# 05_Wifi_Interface.net
KiCad netlist of a schematic drawn in Altium Designer
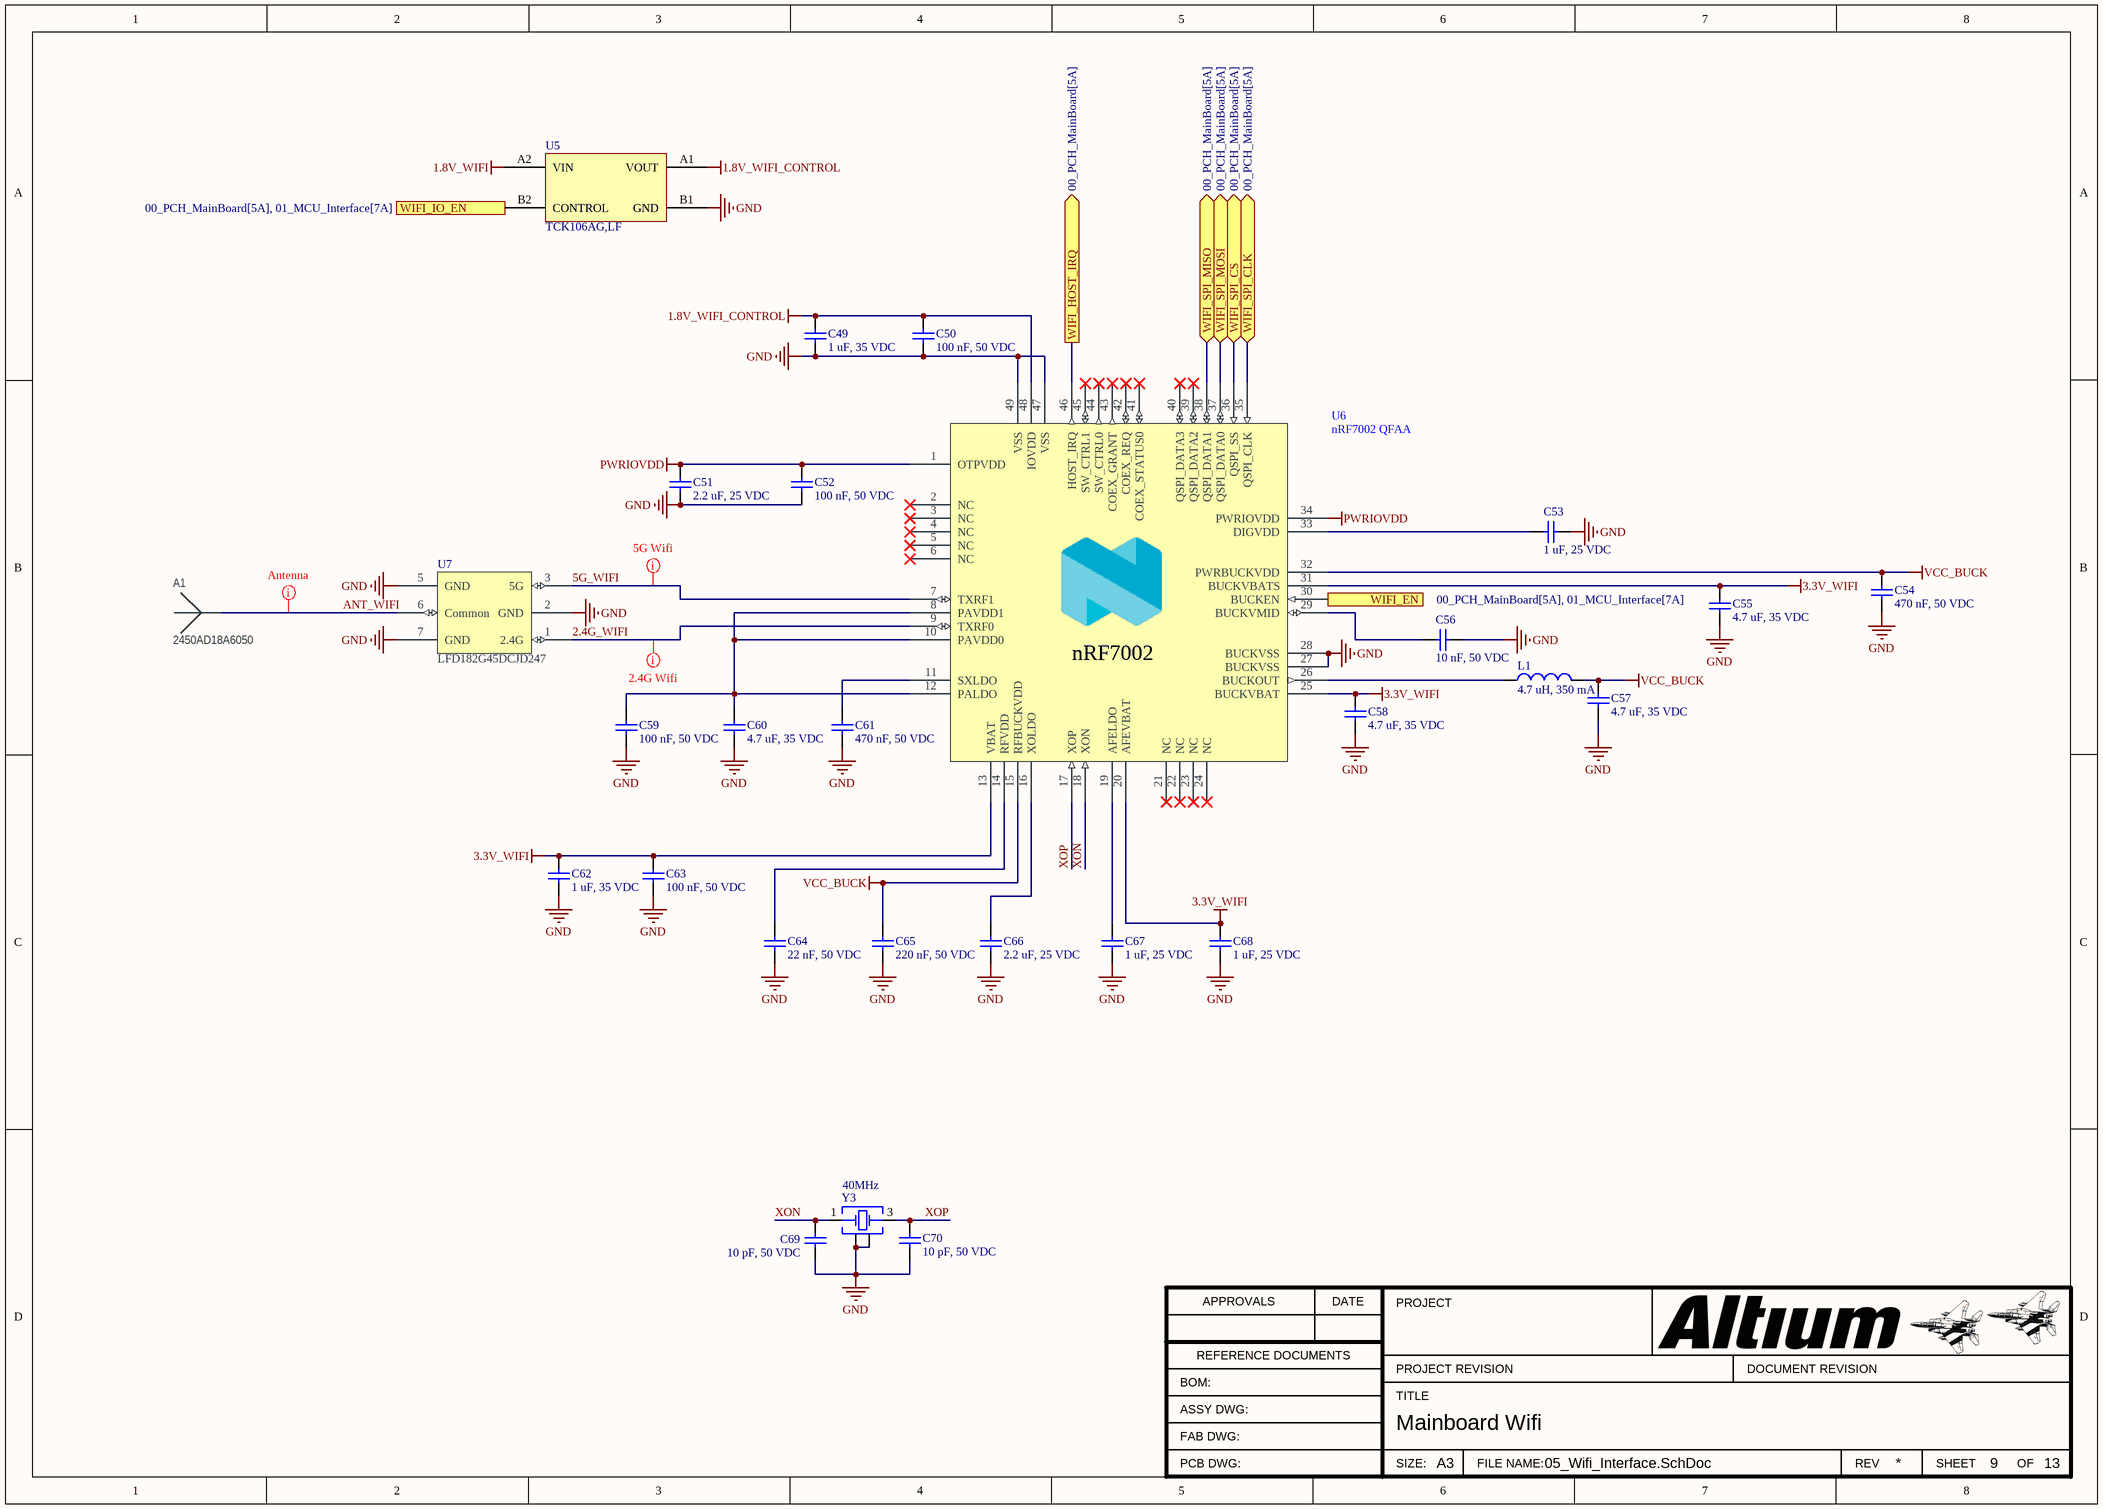
[diagram p0: 05_Wifi_Interface.SchDoc]

(export (version "E")
  (design (tool "Eeschema 10.0.6"))
  (components
    (comp (ref "A1")
      (value "2450AD18A6050")
      (footprint "2450AD18A6050")
      (description "2.4, 5, and 6GHz BT/WiFi6E Mini Antenna, Single-feed, Tri-band, Corner Mount")
      (fields (field (name "MANUFACTURER") "Johanson Technology") (field (name "AUTHOR") "hany"))
      (libsource (lib "Altium_Antenna") (part "2450AD18A6050"))
    )
    (comp (ref "C49")
      (value "1 uF, 35 VDC")
      (footprint "CAP_0603")
      (description "CAP, size 0603, 1 uF, 35 VDC")
      (fields (field (name "TOLERANCE") "+/-10%"))
      (libsource (lib "Altium_Ceramic_Cap") (part "0106031051035"))
    )
    (comp (ref "C50")
      (value "100 nF, 50 VDC")
      (footprint "CAP_0603")
      (description "CAP, size 0603, 100 nF, 50 VDC")
      (fields (field (name "TOLERANCE") "+/-10%"))
      (libsource (lib "Altium_Ceramic_Cap") (part "0106031041050"))
    )
    (comp (ref "C51")
      (value "2.2 uF, 25 VDC")
      (footprint "CAP_0603")
      (description "CAP, size 0603, 2.2 uF, 25 VDC")
      (fields (field (name "TOLERANCE") "+/-10%"))
      (libsource (lib "Altium_Ceramic_Cap") (part "0106032251025"))
    )
    (comp (ref "C52")
      (value "100 nF, 50 VDC")
      (footprint "CAP_0603")
      (description "CAP, size 0603, 100 nF, 50 VDC")
      (fields (field (name "TOLERANCE") "+/-10%"))
      (libsource (lib "Altium_Ceramic_Cap") (part "0106031041050"))
    )
    (comp (ref "C53")
      (value "1 uF, 25 VDC")
      (footprint "CAP_0603")
      (description "CAP, size 0603, 1 uF, 25 VDC")
      (fields (field (name "TOLERANCE") "+/-10%"))
      (libsource (lib "Altium_Ceramic_Cap") (part "0106031051025"))
    )
    (comp (ref "C54")
      (value "470 nF, 50 VDC")
      (footprint "CAP_0603")
      (description "CAP, size 0603, 470 nF, 50 VDC")
      (fields (field (name "TOLERANCE") "+/-10%"))
      (libsource (lib "Altium_Ceramic_Cap") (part "0106034741050"))
    )
    (comp (ref "C55")
      (value "4.7 uF, 35 VDC")
      (footprint "CAP_0603")
      (description "CAP, size 0603, 4.7 uF, 35 VDC")
      (fields (field (name "TOLERANCE") "+/-10%"))
      (libsource (lib "Altium_Ceramic_Cap") (part "0106034751035"))
    )
    (comp (ref "C56")
      (value "10 nF, 50 VDC")
      (footprint "CAP_0603")
      (description "CAP, size 0603, 10 nF, 50 VDC")
      (fields (field (name "TOLERANCE") "+/-5%"))
      (libsource (lib "Altium_Ceramic_Cap") (part "0106031030550"))
    )
    (comp (ref "C57")
      (value "4.7 uF, 35 VDC")
      (footprint "CAP_0603")
      (description "CAP, size 0603, 4.7 uF, 35 VDC")
      (fields (field (name "TOLERANCE") "+/-10%"))
      (libsource (lib "Altium_Ceramic_Cap") (part "0106034751035"))
    )
    (comp (ref "C58")
      (value "4.7 uF, 35 VDC")
      (footprint "CAP_0603")
      (description "CAP, size 0603, 4.7 uF, 35 VDC")
      (fields (field (name "TOLERANCE") "+/-10%"))
      (libsource (lib "Altium_Ceramic_Cap") (part "0106034751035"))
    )
    (comp (ref "C59")
      (value "100 nF, 50 VDC")
      (footprint "CAP_0603")
      (description "CAP, size 0603, 100 nF, 50 VDC")
      (fields (field (name "TOLERANCE") "+/-10%"))
      (libsource (lib "Altium_Ceramic_Cap") (part "0106031041050"))
    )
    (comp (ref "C60")
      (value "4.7 uF, 35 VDC")
      (footprint "CAP_0603")
      (description "CAP, size 0603, 4.7 uF, 35 VDC")
      (fields (field (name "TOLERANCE") "+/-10%"))
      (libsource (lib "Altium_Ceramic_Cap") (part "0106034751035"))
    )
    (comp (ref "C61")
      (value "470 nF, 50 VDC")
      (footprint "CAP_0603")
      (description "CAP, size 0603, 470 nF, 50 VDC")
      (fields (field (name "TOLERANCE") "+/-10%"))
      (libsource (lib "Altium_Ceramic_Cap") (part "0106034741050"))
    )
    (comp (ref "C62")
      (value "1 uF, 35 VDC")
      (footprint "CAP_0603")
      (description "CAP, size 0603, 1 uF, 35 VDC")
      (fields (field (name "TOLERANCE") "+/-10%"))
      (libsource (lib "Altium_Ceramic_Cap") (part "0106031051035"))
    )
    (comp (ref "C63")
      (value "100 nF, 50 VDC")
      (footprint "CAP_0603")
      (description "CAP, size 0603, 100 nF, 50 VDC")
      (fields (field (name "TOLERANCE") "+/-10%"))
      (libsource (lib "Altium_Ceramic_Cap") (part "0106031041050"))
    )
    (comp (ref "C64")
      (value "22 nF, 50 VDC")
      (footprint "CAP_0603")
      (description "CAP, size 0603, 22 nF, 50 VDC")
      (fields (field (name "TOLERANCE") "+/-10%"))
      (libsource (lib "Altium_Ceramic_Cap") (part "0106032231050"))
    )
    (comp (ref "C65")
      (value "220 nF, 50 VDC")
      (footprint "CAP_0603")
      (description "CAP, size 0603, 220 nF, 50 VDC")
      (fields (field (name "TOLERANCE") "+/-10%"))
      (libsource (lib "Altium_Ceramic_Cap") (part "0106032241050"))
    )
    (comp (ref "C66")
      (value "2.2 uF, 25 VDC")
      (footprint "CAP_0603")
      (description "CAP, size 0603, 2.2 uF, 25 VDC")
      (fields (field (name "TOLERANCE") "+/-10%"))
      (libsource (lib "Altium_Ceramic_Cap") (part "0106032251025"))
    )
    (comp (ref "C67")
      (value "1 uF, 25 VDC")
      (footprint "CAP_0603")
      (description "CAP, size 0603, 1 uF, 25 VDC")
      (fields (field (name "TOLERANCE") "+/-10%"))
      (libsource (lib "Altium_Ceramic_Cap") (part "0106031051025"))
    )
    (comp (ref "C68")
      (value "1 uF, 25 VDC")
      (footprint "CAP_0603")
      (description "CAP, size 0603, 1 uF, 25 VDC")
      (fields (field (name "TOLERANCE") "+/-10%"))
      (libsource (lib "Altium_Ceramic_Cap") (part "0106031051025"))
    )
    (comp (ref "C69")
      (value "10 pF, 50 VDC")
      (footprint "CAP_0603")
      (description "CAP, size 0603, 10 pF, 50 VDC")
      (fields (field (name "TOLERANCE") "+/-5%"))
      (libsource (lib "Altium_Ceramic_Cap") (part "0106031000550"))
    )
    (comp (ref "C70")
      (value "10 pF, 50 VDC")
      (footprint "CAP_0603")
      (description "CAP, size 0603, 10 pF, 50 VDC")
      (fields (field (name "TOLERANCE") "+/-5%"))
      (libsource (lib "Altium_Ceramic_Cap") (part "0106031000550"))
    )
    (comp (ref "L1")
      (value "4.7 uH, 350 mA")
      (footprint "0603")
      (description "Inductor SMD, size 0603, 4.7 uH, 350 mA")
      (fields (field (name "TOLERANCE") "20%"))
      (libsource (lib "Altium_Inductor") (part "02060347520350"))
    )
    (comp (ref "U5")
      (value "TCK106AG,LF")
      (footprint "TCK106AG,LF")
      (description "Power Switch ICs - Power Distribution Load Switch IC")
      (fields (field (name "MANUFACTURER") "Toshiba"))
      (libsource (lib "Altium_Power_Supply_IC") (part "TCK106AG,LF"))
    )
    (comp (ref "U6")
      (value "nRF7002 QFAA")
      (footprint "nRF7002")
      (description "Wifi Dual Band Companion chip")
      (fields
        (field (name "PART NUMBER") "nRF7002")
        (field (name "MANUFACTURER") "Nordic Semiconductor")
        (field (name "AUTHOR") "hany")
      )
      (libsource (lib "Nordic") (part "nRF7002"))
    )
    (comp (ref "U7")
      (value "LFD182G45DCJD247")
      (footprint "CAF-50P160X80-6N")
      (description "Signal Conditioning 2.4GHz and 5GHz Diplexer")
      (fields
        (field (name "MANUFACTURER") "Murata")
        (field (name "Comment") "LFD_Diplexer")
        (field (name "AUTHOR") "hany")
      )
      (libsource (lib "MCU_Antenna_Related") (part "LFD182G45DCJD247"))
    )
    (comp (ref "Y3")
      (value "40MHz")
      (footprint "WE-XTAL_CFPX-180")
      (description "WE-XTAL Quartz Crystal, SMT, CFPX-180, 40MHz, +/-20ppm")
      (fields
        (field (name "MANUFACTURER PART NUMBER") "NX3225SA-40M-EXS00A-CS03880")
        (field (name "MANUFACTURER") "NDK")
      )
      (libsource (lib "Altium_XTAL") (part "073525406018"))
    )
  )
  (nets
    (net (code "1") (name "/2.4G_WIFI") (class "Default")
      (node (ref "U6") (pin "9") (pinfunction "TXRF0_9") (pintype "bidirectional"))
      (node (ref "U7") (pin "1") (pinfunction "2.4G_1") (pintype "bidirectional"))
    )
    (net (code "2") (name "/5G_WIFI") (class "Default")
      (node (ref "U6") (pin "7") (pinfunction "TXRF1_7") (pintype "bidirectional"))
      (node (ref "U7") (pin "3") (pinfunction "5G_3") (pintype "bidirectional"))
    )
    (net (code "3") (name "/ANT_WIFI") (class "Default")
      (node (ref "A1") (pin "1") (pinfunction "1_1") (pintype "passive"))
      (node (ref "U7") (pin "6") (pinfunction "Common_6") (pintype "bidirectional"))
    )
    (net (code "4") (name "/WIFI_EN") (class "Default")
      (node (ref "U6") (pin "30") (pinfunction "BUCKEN_30") (pintype "input"))
    )
    (net (code "5") (name "/WIFI_HOST_IRQ") (class "Default")
      (node (ref "U6") (pin "46") (pinfunction "HOST_IRQ_46") (pintype "output"))
    )
    (net (code "6") (name "/WIFI_IO_EN") (class "Default")
      (node (ref "U5") (pin "B2") (pinfunction "CONTROL_B2") (pintype "passive"))
    )
    (net (code "7") (name "/WIFI_SPI_CLK") (class "Default")
      (node (ref "U6") (pin "35") (pinfunction "QSPI_CLK_35") (pintype "input"))
    )
    (net (code "8") (name "/WIFI_SPI_CS") (class "Default")
      (node (ref "U6") (pin "36") (pinfunction "QSPI_SS_36") (pintype "input"))
    )
    (net (code "9") (name "/WIFI_SPI_MISO") (class "Default")
      (node (ref "U6") (pin "38") (pinfunction "QSPI_DATA1_38") (pintype "bidirectional"))
    )
    (net (code "10") (name "/WIFI_SPI_MOSI") (class "Default")
      (node (ref "U6") (pin "37") (pinfunction "QSPI_DATA0_37") (pintype "bidirectional"))
    )
    (net (code "11") (name "/XON") (class "Default")
      (node (ref "C69") (pin "2") (pinfunction "2_2") (pintype "passive"))
      (node (ref "U6") (pin "18") (pinfunction "XON_18") (pintype "input"))
      (node (ref "Y3") (pin "1") (pinfunction "Crystal_1") (pintype "passive"))
    )
    (net (code "12") (name "/XOP") (class "Default")
      (node (ref "C70") (pin "2") (pinfunction "2_2") (pintype "passive"))
      (node (ref "U6") (pin "17") (pinfunction "XOP_17") (pintype "input"))
      (node (ref "Y3") (pin "3") (pinfunction "Crystal_3") (pintype "passive"))
    )
    (net (code "13") (name "1.8V_WIFI") (class "Default")
      (node (ref "U5") (pin "A2") (pinfunction "VIN_A2") (pintype "passive"))
    )
    (net (code "14") (name "1.8V_WIFI_CONTROL") (class "Default")
      (node (ref "C49") (pin "2") (pinfunction "2_2") (pintype "passive"))
      (node (ref "C50") (pin "2") (pinfunction "2_2") (pintype "passive"))
      (node (ref "U5") (pin "A1") (pinfunction "VOUT_A1") (pintype "passive"))
      (node (ref "U6") (pin "48") (pinfunction "IOVDD_48") (pintype "power_in"))
    )
    (net (code "15") (name "3.3V_WIFI") (class "Default")
      (node (ref "C55") (pin "2") (pinfunction "2_2") (pintype "passive"))
      (node (ref "C58") (pin "2") (pinfunction "2_2") (pintype "passive"))
      (node (ref "C62") (pin "2") (pinfunction "2_2") (pintype "passive"))
      (node (ref "C63") (pin "2") (pinfunction "2_2") (pintype "passive"))
      (node (ref "C68") (pin "2") (pinfunction "2_2") (pintype "passive"))
      (node (ref "U6") (pin "13") (pinfunction "VBAT_13") (pintype "power_in"))
      (node (ref "U6") (pin "20") (pinfunction "AFEVBAT_20") (pintype "power_in"))
      (node (ref "U6") (pin "25") (pinfunction "BUCKVBAT_25") (pintype "power_in"))
      (node (ref "U6") (pin "31") (pinfunction "BUCKVBATS_31") (pintype "power_in"))
    )
    (net (code "16") (name "GND") (class "Default")
      (node (ref "C49") (pin "1") (pinfunction "1_1") (pintype "passive"))
      (node (ref "C50") (pin "1") (pinfunction "1_1") (pintype "passive"))
      (node (ref "C51") (pin "1") (pinfunction "1_1") (pintype "passive"))
      (node (ref "C52") (pin "1") (pinfunction "1_1") (pintype "passive"))
      (node (ref "C53") (pin "2") (pinfunction "2_2") (pintype "passive"))
      (node (ref "C54") (pin "1") (pinfunction "1_1") (pintype "passive"))
      (node (ref "C55") (pin "1") (pinfunction "1_1") (pintype "passive"))
      (node (ref "C56") (pin "2") (pinfunction "2_2") (pintype "passive"))
      (node (ref "C57") (pin "1") (pinfunction "1_1") (pintype "passive"))
      (node (ref "C58") (pin "1") (pinfunction "1_1") (pintype "passive"))
      (node (ref "C59") (pin "1") (pinfunction "1_1") (pintype "passive"))
      (node (ref "C60") (pin "1") (pinfunction "1_1") (pintype "passive"))
      (node (ref "C61") (pin "1") (pinfunction "1_1") (pintype "passive"))
      (node (ref "C62") (pin "1") (pinfunction "1_1") (pintype "passive"))
      (node (ref "C63") (pin "1") (pinfunction "1_1") (pintype "passive"))
      (node (ref "C64") (pin "1") (pinfunction "1_1") (pintype "passive"))
      (node (ref "C65") (pin "1") (pinfunction "1_1") (pintype "passive"))
      (node (ref "C66") (pin "1") (pinfunction "1_1") (pintype "passive"))
      (node (ref "C67") (pin "1") (pinfunction "1_1") (pintype "passive"))
      (node (ref "C68") (pin "1") (pinfunction "1_1") (pintype "passive"))
      (node (ref "C69") (pin "1") (pinfunction "1_1") (pintype "passive"))
      (node (ref "C70") (pin "1") (pinfunction "1_1") (pintype "passive"))
      (node (ref "U5") (pin "B1") (pinfunction "GND_B1") (pintype "passive"))
      (node (ref "U6") (pin "27") (pinfunction "BUCKVSS_27") (pintype "power_in"))
      (node (ref "U6") (pin "28") (pinfunction "BUCKVSS_28") (pintype "power_in"))
      (node (ref "U6") (pin "47") (pinfunction "VSS_47") (pintype "passive"))
      (node (ref "U6") (pin "49") (pinfunction "VSS_49") (pintype "power_in"))
      (node (ref "U7") (pin "2") (pinfunction "GND_2") (pintype "power_in"))
      (node (ref "U7") (pin "5") (pinfunction "GND_5") (pintype "power_in"))
      (node (ref "U7") (pin "7") (pinfunction "GND_7") (pintype "power_in"))
      (node (ref "Y3") (pin "2") (pinfunction "GND_2") (pintype "passive"))
      (node (ref "Y3") (pin "4") (pinfunction "GND_4") (pintype "passive"))
    )
    (net (code "17") (name "Net-(U6-AFELDO)") (class "Default")
      (node (ref "C67") (pin "2") (pinfunction "2_2") (pintype "passive"))
      (node (ref "U6") (pin "19") (pinfunction "AFELDO_19") (pintype "power_in"))
    )
    (net (code "18") (name "Net-(U6-BUCKOUT)") (class "Default")
      (node (ref "L1") (pin "1") (pinfunction "1_1") (pintype "passive"))
      (node (ref "U6") (pin "26") (pinfunction "BUCKOUT_26") (pintype "output"))
    )
    (net (code "19") (name "Net-(U6-BUCKVMID)") (class "Default")
      (node (ref "C56") (pin "1") (pinfunction "1_1") (pintype "passive"))
      (node (ref "U6") (pin "29") (pinfunction "BUCKVMID_29") (pintype "bidirectional"))
    )
    (net (code "20") (name "Net-(U6-DIGVDD)") (class "Default")
      (node (ref "C53") (pin "1") (pinfunction "1_1") (pintype "passive"))
      (node (ref "U6") (pin "33") (pinfunction "DIGVDD_33") (pintype "power_in"))
    )
    (net (code "21") (name "Net-(U6-PALDO)") (class "Default")
      (node (ref "C59") (pin "2") (pinfunction "2_2") (pintype "passive"))
      (node (ref "C60") (pin "2") (pinfunction "2_2") (pintype "passive"))
      (node (ref "U6") (pin "10") (pinfunction "PAVDD0_10") (pintype "power_in"))
      (node (ref "U6") (pin "12") (pinfunction "PALDO_12") (pintype "power_in"))
      (node (ref "U6") (pin "8") (pinfunction "PAVDD1_8") (pintype "power_in"))
    )
    (net (code "22") (name "Net-(U6-RFVDD)") (class "Default")
      (node (ref "C64") (pin "2") (pinfunction "2_2") (pintype "passive"))
      (node (ref "U6") (pin "14") (pinfunction "RFVDD_14") (pintype "power_in"))
    )
    (net (code "23") (name "Net-(U6-SXLDO)") (class "Default")
      (node (ref "C61") (pin "2") (pinfunction "2_2") (pintype "passive"))
      (node (ref "U6") (pin "11") (pinfunction "SXLDO_11") (pintype "power_in"))
    )
    (net (code "24") (name "Net-(U6-XOLDO)") (class "Default")
      (node (ref "C66") (pin "2") (pinfunction "2_2") (pintype "passive"))
      (node (ref "U6") (pin "16") (pinfunction "XOLDO_16") (pintype "power_in"))
    )
    (net (code "25") (name "PWRIOVDD") (class "Default")
      (node (ref "C51") (pin "2") (pinfunction "2_2") (pintype "passive"))
      (node (ref "C52") (pin "2") (pinfunction "2_2") (pintype "passive"))
      (node (ref "U6") (pin "1") (pinfunction "OTPVDD_1") (pintype "power_in"))
      (node (ref "U6") (pin "34") (pinfunction "PWRIOVDD_34") (pintype "power_in"))
    )
    (net (code "26") (name "VCC_BUCK") (class "Default")
      (node (ref "C54") (pin "2") (pinfunction "2_2") (pintype "passive"))
      (node (ref "C57") (pin "2") (pinfunction "2_2") (pintype "passive"))
      (node (ref "C65") (pin "2") (pinfunction "2_2") (pintype "passive"))
      (node (ref "L1") (pin "2") (pinfunction "2_2") (pintype "passive"))
      (node (ref "U6") (pin "15") (pinfunction "RFBUCKVDD_15") (pintype "power_in"))
      (node (ref "U6") (pin "32") (pinfunction "PWRBUCKVDD_32") (pintype "power_in"))
    )
    (net (code "27") (name "unconnected-(U6-COEX_GRANT-Pad43)") (class "Default")
      (node (ref "U6") (pin "43") (pinfunction "COEX_GRANT_43") (pintype "output+no_connect"))
    )
    (net (code "28") (name "unconnected-(U6-COEX_REQ-Pad42)") (class "Default")
      (node (ref "U6") (pin "42") (pinfunction "COEX_REQ_42") (pintype "bidirectional+no_connect"))
    )
    (net (code "29") (name "unconnected-(U6-COEX_STATUS0-Pad41)") (class "Default")
      (node (ref "U6") (pin "41") (pinfunction "COEX_STATUS0_41") (pintype "bidirectional+no_connect"))
    )
    (net (code "30") (name "unconnected-(U6-NC-Pad2)") (class "Default")
      (node (ref "U6") (pin "2") (pinfunction "NC_2") (pintype "passive+no_connect"))
    )
    (net (code "31") (name "unconnected-(U6-NC-Pad3)") (class "Default")
      (node (ref "U6") (pin "3") (pinfunction "NC_3") (pintype "passive+no_connect"))
    )
    (net (code "32") (name "unconnected-(U6-NC-Pad4)") (class "Default")
      (node (ref "U6") (pin "4") (pinfunction "NC_4") (pintype "passive+no_connect"))
    )
    (net (code "33") (name "unconnected-(U6-NC-Pad5)") (class "Default")
      (node (ref "U6") (pin "5") (pinfunction "NC_5") (pintype "passive+no_connect"))
    )
    (net (code "34") (name "unconnected-(U6-NC-Pad6)") (class "Default")
      (node (ref "U6") (pin "6") (pinfunction "NC_6") (pintype "passive+no_connect"))
    )
    (net (code "35") (name "unconnected-(U6-NC-Pad21)") (class "Default")
      (node (ref "U6") (pin "21") (pinfunction "NC_21") (pintype "passive+no_connect"))
    )
    (net (code "36") (name "unconnected-(U6-NC-Pad22)") (class "Default")
      (node (ref "U6") (pin "22") (pinfunction "NC_22") (pintype "passive+no_connect"))
    )
    (net (code "37") (name "unconnected-(U6-NC-Pad23)") (class "Default")
      (node (ref "U6") (pin "23") (pinfunction "NC_23") (pintype "passive+no_connect"))
    )
    (net (code "38") (name "unconnected-(U6-NC-Pad24)") (class "Default")
      (node (ref "U6") (pin "24") (pinfunction "NC_24") (pintype "passive+no_connect"))
    )
    (net (code "39") (name "unconnected-(U6-QSPI_DATA2-Pad39)") (class "Default")
      (node (ref "U6") (pin "39") (pinfunction "QSPI_DATA2_39") (pintype "bidirectional+no_connect"))
    )
    (net (code "40") (name "unconnected-(U6-QSPI_DATA3-Pad40)") (class "Default")
      (node (ref "U6") (pin "40") (pinfunction "QSPI_DATA3_40") (pintype "bidirectional+no_connect"))
    )
    (net (code "41") (name "unconnected-(U6-SW_CTRL0-Pad44)") (class "Default")
      (node (ref "U6") (pin "44") (pinfunction "SW_CTRL0_44") (pintype "output+no_connect"))
    )
    (net (code "42") (name "unconnected-(U6-SW_CTRL1-Pad45)") (class "Default")
      (node (ref "U6") (pin "45") (pinfunction "SW_CTRL1_45") (pintype "bidirectional+no_connect"))
    )
  )
)
